# NILINET_POWER_PIR.net
KiCad netlist of a schematic drawn in Altium Designer
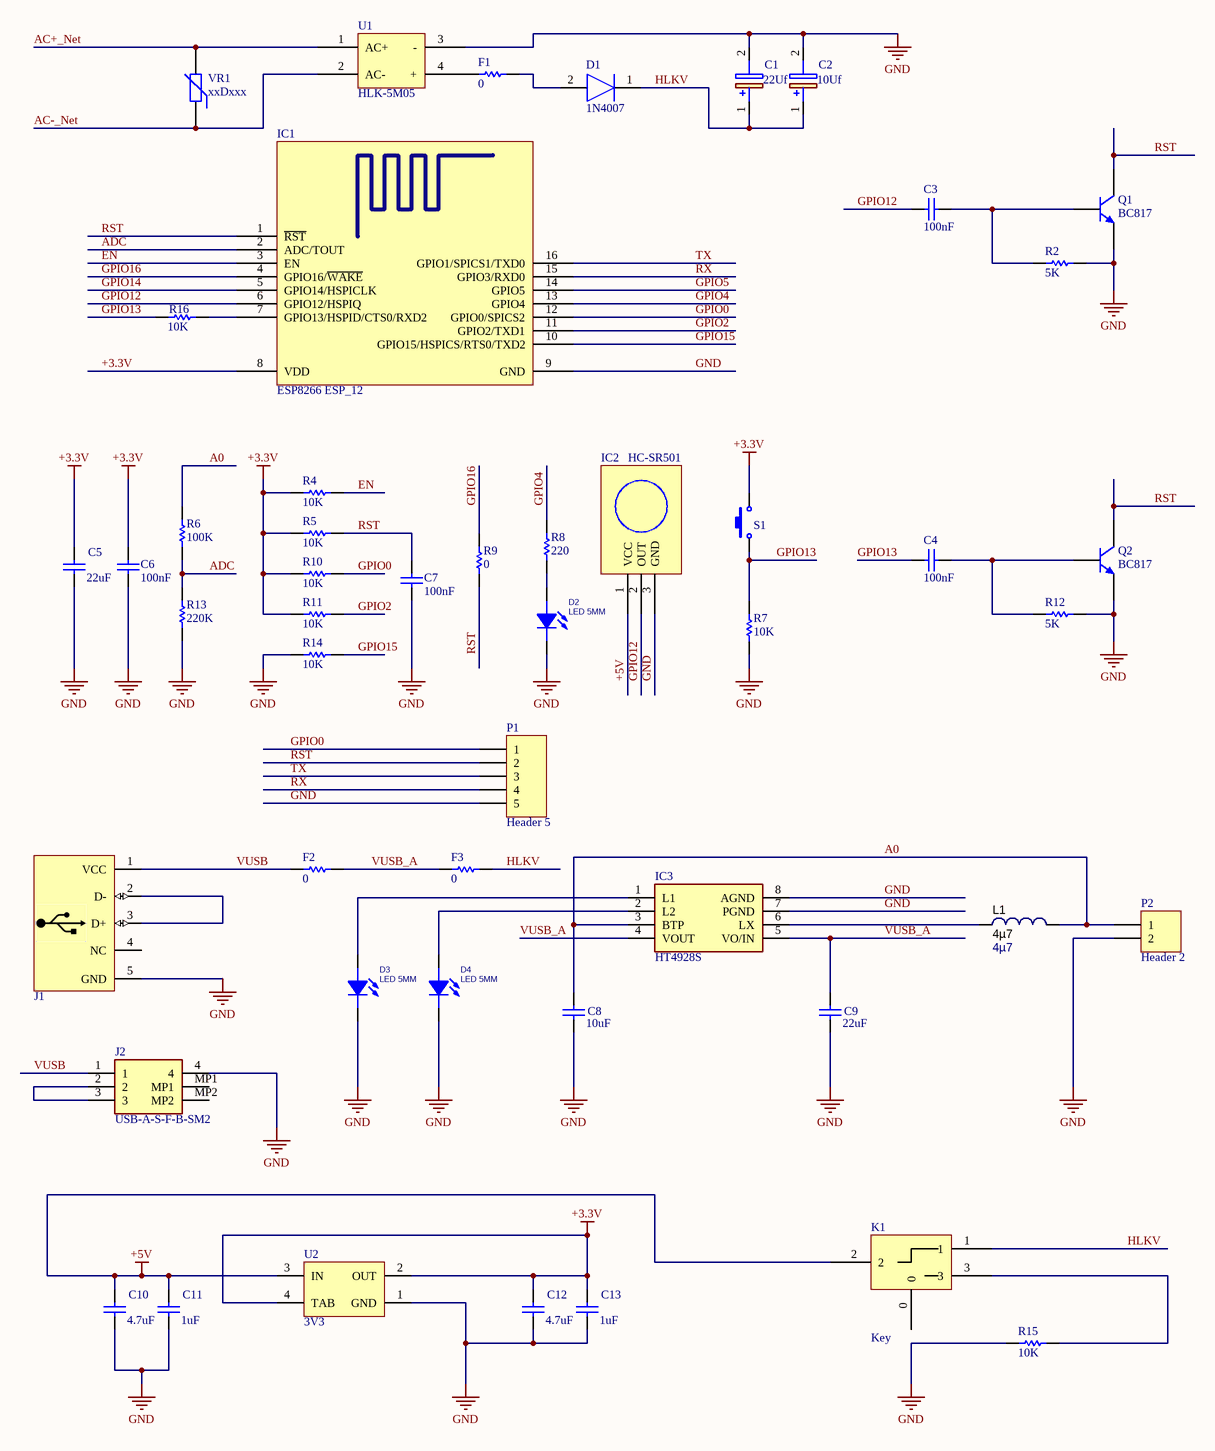
[diagram p0: NILINET_POWER_PIR.SchDoc]

(export (version "E")
  (design (tool "Eeschema 10.0.6"))
  (components
    (comp (ref "C1")
      (value "22Uf")
      (footprint "SamacSys:UWT(4X5.4)")
      (description "Capacitor Polarised")
      (fields
        (field (name "MANUFACTURER_PART_NUMBER") "UWT1C100MCL1GB")
        (field (name "MOUSER PART NUMBER") "647-UWT1C100MCL1B")
      )
      (libsource (lib "*") (part "UWT1C100MCL1GB"))
    )
    (comp (ref "C2")
      (value "10Uf")
      (footprint "SamacSys:UWT(4X5.4)")
      (description "Capacitor Polarised")
      (fields
        (field (name "MANUFACTURER_PART_NUMBER") "UWT1C100MCL1GB")
        (field (name "MOUSER PART NUMBER") "647-UWT1C100MCL1B")
      )
      (libsource (lib "*") (part "UWT1C100MCL1GB"))
    )
    (comp (ref "C3")
      (value "100nF")
      (footprint "CAP0603")
      (description "TOTAL CAPACITOR SMD PACK")
      (fields (field (name "DESIGNER") "Abbas Basereh"))
      (libsource (lib "Altium") (part "CAP SMD PACKAGE"))
    )
    (comp (ref "C4")
      (value "100nF")
      (footprint "CAP0603")
      (description "TOTAL CAPACITOR SMD PACK")
      (fields (field (name "DESIGNER") "Abbas Basereh"))
      (libsource (lib "Altium") (part "CAP SMD PACKAGE"))
    )
    (comp (ref "C5")
      (value "22uF")
      (footprint "CAP0805")
      (description "TOTAL CAPACITOR SMD PACK")
      (fields (field (name "DESIGNER") "Abbas Basereh"))
      (libsource (lib "Altium") (part "CAP SMD PACKAGE"))
    )
    (comp (ref "C6")
      (value "100nF")
      (footprint "CAP0603")
      (description "TOTAL CAPACITOR SMD PACK")
      (fields (field (name "DESIGNER") "Abbas Basereh"))
      (libsource (lib "Altium") (part "CAP SMD PACKAGE"))
    )
    (comp (ref "C7")
      (value "100nF")
      (footprint "CAP0603")
      (description "TOTAL CAPACITOR SMD PACK")
      (fields (field (name "DESIGNER") "Abbas Basereh"))
      (libsource (lib "Altium") (part "CAP SMD PACKAGE"))
    )
    (comp (ref "C8")
      (value "10uF")
      (footprint "CAP0805")
      (description "TOTAL CAPACITOR SMD PACK")
      (fields (field (name "DESIGNER") "Abbas Basereh"))
      (libsource (lib "Altium") (part "CAP SMD PACKAGE"))
    )
    (comp (ref "C9")
      (value "22uF")
      (footprint "CAP0805")
      (description "TOTAL CAPACITOR SMD PACK")
      (fields (field (name "DESIGNER") "Abbas Basereh"))
      (libsource (lib "Altium") (part "CAP SMD PACKAGE"))
    )
    (comp (ref "C10")
      (value "4.7uF")
      (footprint "CAP0805")
      (description "TOTAL CAPACITOR SMD PACK")
      (fields (field (name "DESIGNER") "Abbas Basereh"))
      (libsource (lib "Altium") (part "CAP SMD PACKAGE"))
    )
    (comp (ref "C11")
      (value "1uF")
      (footprint "CAP0805")
      (description "TOTAL CAPACITOR SMD PACK")
      (fields (field (name "DESIGNER") "Abbas Basereh"))
      (libsource (lib "Altium") (part "CAP SMD PACKAGE"))
    )
    (comp (ref "C12")
      (value "4.7uF")
      (footprint "CAP0805")
      (description "TOTAL CAPACITOR SMD PACK")
      (fields (field (name "DESIGNER") "Abbas Basereh"))
      (libsource (lib "Altium") (part "CAP SMD PACKAGE"))
    )
    (comp (ref "C13")
      (value "1uF")
      (footprint "CAP0805")
      (description "TOTAL CAPACITOR SMD PACK")
      (fields (field (name "DESIGNER") "Abbas Basereh"))
      (libsource (lib "Altium") (part "CAP SMD PACKAGE"))
    )
    (comp (ref "D1")
      (value "1N4007")
      (footprint "SamacSys:DIOM5327X242N")
      (description "Diode")
      (libsource (lib "*") (part "1N4007"))
    )
    (comp (ref "D2")
      (value "LED 5MM")
      (footprint "LED5MM_BLUE")
      (description "Light Emitting Diode")
      (fields (field (name "DESIGNER") "Abbas Basereh"))
      (libsource (lib "Altium") (part "LED 5MM"))
    )
    (comp (ref "D3")
      (value "LED 5MM")
      (footprint "LED5MM_RED")
      (description "Light Emitting Diode")
      (fields (field (name "DESIGNER") "Abbas Basereh"))
      (libsource (lib "Altium") (part "LED 5MM"))
    )
    (comp (ref "D4")
      (value "LED 5MM")
      (footprint "LED5MM_GRN")
      (description "Light Emitting Diode")
      (fields (field (name "DESIGNER") "Abbas Basereh"))
      (libsource (lib "Altium") (part "LED 5MM"))
    )
    (comp (ref "F1")
      (value "0")
      (footprint "RES0805")
      (description "TOTAL SMD RESISTOR PACK")
      (fields (field (name "DESIGNER") "Abbas Basereh"))
      (libsource (lib "Altium") (part "RES SMD PACKAGE"))
    )
    (comp (ref "F2")
      (value "0")
      (footprint "RES0805")
      (description "TOTAL SMD RESISTOR PACK")
      (fields (field (name "DESIGNER") "Abbas Basereh"))
      (libsource (lib "Altium") (part "RES SMD PACKAGE"))
    )
    (comp (ref "F3")
      (value "0")
      (footprint "RES0805")
      (description "TOTAL SMD RESISTOR PACK")
      (fields (field (name "DESIGNER") "Abbas Basereh"))
      (libsource (lib "Altium") (part "RES SMD PACKAGE"))
    )
    (comp (ref "IC1")
      (value "ESP8266 ESP_12")
      (footprint "ESP8266 ESP_12")
      (description "ESP8266 ESP-12")
      (fields (field (name "PUBLISHER") "Cynetik Group") (field (name "LATESTREVIEWER") "Zion Blue"))
      (libsource (lib "ESP8266") (part "ESP8266 ESP_12"))
    )
    (comp (ref "IC2")
      (value "HC-SR501")
      (footprint "jumper selector")
      (libsource (lib "HC-SR501") (part "HC-SR501"))
    )
    (comp (ref "IC3")
      (value "HT4928S")
      (footprint "SamacSys:SOIC127P600X180-8N")
      (description "Integrated Circuit")
      (libsource (lib "*") (part "HT4928S"))
    )
    (comp (ref "J1")
      (value "USB Connector")
      (footprint "MicroUSB111")
      (description "USB Connector MICRO-B Type")
      (fields (field (name "DESIGNER") "ABBAS BASEREH") (field (name "PUBLISHER") "ABBAS BASEREH"))
      (libsource (lib "Altium") (part "USB MICRO"))
    )
    (comp (ref "J2")
      (value "USB-A-S-F-B-SM2")
      (footprint "USBASFBSM3")
      (description "Connector")
      (fields (field (name "MOUSER PART NUMBER") "200-USBASFBSM2") (field (name "RS PART NUMBER") "1803451"))
      (libsource (lib "*") (part "USB-A-S-F-B-SM2"))
    )
    (comp (ref "K1") (value "Key") (footprint "Key") (libsource (lib "Key") (part "Key")))
    (comp (ref "L1")
      (value "4µ7")
      (footprint "Inductor SMD 3x3.2mm")
      (description "Inductor 4.7µH SMD 3x3.2mm")
      (fields (field (name "TOLERANCE") "±20%") (field (name "ALTIUM_VALUE") "4µ7"))
      (libsource (lib "General 1") (part "Inductor 4.7µH SMD 3x3.2mm"))
    )
    (comp (ref "P1")
      (value "Header 5")
      (footprint "HDR1X5")
      (description "Header, 5-Pin")
      (fields (field (name "PUBLISHER") "Altium Limited"))
      (libsource (lib "Altium") (part "Header 5"))
    )
    (comp (ref "P2")
      (value "Header 2")
      (footprint "HDR1X2")
      (description "Header, 2-Pin")
      (fields (field (name "PUBLISHER") "Altium Limited"))
      (libsource (lib "Altium") (part "Header 2"))
    )
    (comp (ref "Q1")
      (value "BC817")
      (footprint "SOT23_N")
      (description "45 V, 500 mA NPN general-purpose transistors")
      (fields (field (name "PUBLISHER") "Abbas Basereh"))
      (libsource (lib "General 1") (part "BC817"))
    )
    (comp (ref "Q2")
      (value "BC817")
      (footprint "SOT23_N")
      (description "45 V, 500 mA NPN general-purpose transistors")
      (fields (field (name "PUBLISHER") "Abbas Basereh"))
      (libsource (lib "General 1") (part "BC817"))
    )
    (comp (ref "R2")
      (value "5K")
      (footprint "RES0603")
      (description "TOTAL SMD RESISTOR PACK")
      (fields (field (name "DESIGNER") "Abbas Basereh"))
      (libsource (lib "Altium") (part "RES SMD PACKAGE"))
    )
    (comp (ref "R4")
      (value "10K")
      (footprint "RES0603")
      (description "TOTAL SMD RESISTOR PACK")
      (fields (field (name "DESIGNER") "Abbas Basereh"))
      (libsource (lib "Altium") (part "RES SMD PACKAGE"))
    )
    (comp (ref "R5")
      (value "10K")
      (footprint "RES0603")
      (description "TOTAL SMD RESISTOR PACK")
      (fields (field (name "DESIGNER") "Abbas Basereh"))
      (libsource (lib "Altium") (part "RES SMD PACKAGE"))
    )
    (comp (ref "R6")
      (value "100K")
      (footprint "RES0603")
      (description "TOTAL SMD RESISTOR PACK")
      (fields (field (name "DESIGNER") "Abbas Basereh"))
      (libsource (lib "Altium") (part "RES SMD PACKAGE"))
    )
    (comp (ref "R7")
      (value "10K")
      (footprint "RES0603")
      (description "TOTAL SMD RESISTOR PACK")
      (fields (field (name "DESIGNER") "Abbas Basereh"))
      (libsource (lib "Altium") (part "RES SMD PACKAGE"))
    )
    (comp (ref "R8")
      (value "220")
      (footprint "RES0603")
      (description "TOTAL SMD RESISTOR PACK")
      (fields (field (name "DESIGNER") "Abbas Basereh"))
      (libsource (lib "Altium") (part "RES SMD PACKAGE"))
    )
    (comp (ref "R9")
      (value "0")
      (footprint "RES0603")
      (description "TOTAL SMD RESISTOR PACK")
      (fields (field (name "DESIGNER") "Abbas Basereh"))
      (libsource (lib "Altium") (part "RES SMD PACKAGE"))
    )
    (comp (ref "R10")
      (value "10K")
      (footprint "RES0603")
      (description "TOTAL SMD RESISTOR PACK")
      (fields (field (name "DESIGNER") "Abbas Basereh"))
      (libsource (lib "Altium") (part "RES SMD PACKAGE"))
    )
    (comp (ref "R11")
      (value "10K")
      (footprint "RES0603")
      (description "TOTAL SMD RESISTOR PACK")
      (fields (field (name "DESIGNER") "Abbas Basereh"))
      (libsource (lib "Altium") (part "RES SMD PACKAGE"))
    )
    (comp (ref "R12")
      (value "5K")
      (footprint "RES0603")
      (description "TOTAL SMD RESISTOR PACK")
      (fields (field (name "DESIGNER") "Abbas Basereh"))
      (libsource (lib "Altium") (part "RES SMD PACKAGE"))
    )
    (comp (ref "R13")
      (value "220K")
      (footprint "RES0603")
      (description "TOTAL SMD RESISTOR PACK")
      (fields (field (name "DESIGNER") "Abbas Basereh"))
      (libsource (lib "Altium") (part "RES SMD PACKAGE"))
    )
    (comp (ref "R14")
      (value "10K")
      (footprint "RES0603")
      (description "TOTAL SMD RESISTOR PACK")
      (fields (field (name "DESIGNER") "Abbas Basereh"))
      (libsource (lib "Altium") (part "RES SMD PACKAGE"))
    )
    (comp (ref "R15")
      (value "10K")
      (footprint "RES0603")
      (description "TOTAL SMD RESISTOR PACK")
      (fields (field (name "DESIGNER") "Abbas Basereh"))
      (libsource (lib "Altium") (part "RES SMD PACKAGE"))
    )
    (comp (ref "R16")
      (value "10K")
      (footprint "RES0603")
      (description "TOTAL SMD RESISTOR PACK")
      (fields (field (name "DESIGNER") "Abbas Basereh"))
      (libsource (lib "Altium") (part "RES SMD PACKAGE"))
    )
    (comp (ref "S1")
      (value "Switch PB")
      (footprint "SwitchRight")
      (description "Push Button Switch")
      (libsource (lib "Altium") (part "Switch PB"))
    )
    (comp (ref "U1") (value "HLK-5M05") (footprint "HLK-5M05") (libsource (lib "HLK-5M05") (part "HLK-PM01")))
    (comp (ref "U2")
      (value "3V3")
      (footprint "SOT223")
      (description "x.x Volt, 800mA Low-Dropout Linear Regulator, 4-pin SOT-223")
      (fields (field (name "DESIGNER") "Ali Hafizi"))
      (libsource (lib "Altium") (part "AMS1117-x.x"))
    )
    (comp (ref "VR1")
      (value "xxDxxx")
      (footprint "10D XXX")
      (description "VARISTORS")
      (fields
        (field (name "MANUFACTURER") "china-canada-philipina")
        (field (name "DESIGNER") "Abbas Basereh")
        (field (name "PUBLISHER") "ABBAS BASEREH")
      )
      (libsource (lib "Altium") (part "VARISTOR (VDR)"))
    )
  )
  (nets
    (net (code "1") (name "+3.3V") (class "Default")
      (node (ref "C12") (pin "2") (pinfunction "2_2") (pintype "passive"))
      (node (ref "C13") (pin "2") (pinfunction "2_2") (pintype "passive"))
      (node (ref "C5") (pin "2") (pinfunction "2_2") (pintype "passive"))
      (node (ref "C6") (pin "2") (pinfunction "2_2") (pintype "passive"))
      (node (ref "IC1") (pin "8") (pinfunction "VDD_8") (pintype "passive"))
      (node (ref "R10") (pin "2") (pinfunction "2_2") (pintype "passive"))
      (node (ref "R11") (pin "2") (pinfunction "2_2") (pintype "passive"))
      (node (ref "R4") (pin "2") (pinfunction "2_2") (pintype "passive"))
      (node (ref "R5") (pin "2") (pinfunction "2_2") (pintype "passive"))
      (node (ref "S1") (pin "2") (pinfunction "2_2") (pintype "passive"))
      (node (ref "U2") (pin "2") (pinfunction "OUT_2") (pintype "power_in"))
      (node (ref "U2") (pin "4") (pinfunction "TAB_4") (pintype "power_in"))
    )
    (net (code "2") (name "+5V") (class "Default")
      (node (ref "C10") (pin "2") (pinfunction "2_2") (pintype "passive"))
      (node (ref "C11") (pin "2") (pinfunction "2_2") (pintype "passive"))
      (node (ref "IC2") (pin "1") (pinfunction "VCC_1") (pintype "passive"))
      (node (ref "K1") (pin "2") (pinfunction "2_2") (pintype "passive"))
      (node (ref "U2") (pin "3") (pinfunction "IN_3") (pintype "power_in"))
    )
    (net (code "3") (name "/A0") (class "Default")
      (node (ref "C8") (pin "2") (pinfunction "2_2") (pintype "passive"))
      (node (ref "IC3") (pin "3") (pinfunction "BTP_3") (pintype "passive"))
      (node (ref "L1") (pin "2") (pinfunction "2_2") (pintype "passive"))
      (node (ref "P2") (pin "1") (pinfunction "1_1") (pintype "passive"))
      (node (ref "R6") (pin "2") (pinfunction "2_2") (pintype "passive"))
    )
    (net (code "4") (name "/AC+_Net") (class "Default")
      (node (ref "U1") (pin "1") (pinfunction "AC+_1") (pintype "passive"))
      (node (ref "VR1") (pin "2") (pinfunction "2_2") (pintype "passive"))
    )
    (net (code "5") (name "/AC-_Net") (class "Default")
      (node (ref "U1") (pin "2") (pinfunction "AC-_2") (pintype "passive"))
      (node (ref "VR1") (pin "1") (pinfunction "1_1") (pintype "passive"))
    )
    (net (code "6") (name "/ADC") (class "Default")
      (node (ref "IC1") (pin "2") (pinfunction "ADC/TOUT_2") (pintype "passive"))
      (node (ref "R13") (pin "2") (pinfunction "2_2") (pintype "passive"))
      (node (ref "R6") (pin "1") (pinfunction "1_1") (pintype "passive"))
    )
    (net (code "7") (name "/EN") (class "Default")
      (node (ref "IC1") (pin "3") (pinfunction "EN_3") (pintype "passive"))
      (node (ref "R4") (pin "1") (pinfunction "1_1") (pintype "passive"))
    )
    (net (code "8") (name "/GPIO0") (class "Default")
      (node (ref "IC1") (pin "12") (pinfunction "GPIO0/SPICS2_12") (pintype "passive"))
      (node (ref "P1") (pin "1") (pinfunction "1_1") (pintype "passive"))
      (node (ref "R10") (pin "1") (pinfunction "1_1") (pintype "passive"))
    )
    (net (code "9") (name "/GPIO2") (class "Default")
      (node (ref "IC1") (pin "11") (pinfunction "GPIO2/TXD1_11") (pintype "passive"))
      (node (ref "R11") (pin "1") (pinfunction "1_1") (pintype "passive"))
    )
    (net (code "10") (name "/GPIO4") (class "Default")
      (node (ref "IC1") (pin "13") (pinfunction "GPIO4_13") (pintype "passive"))
      (node (ref "R8") (pin "1") (pinfunction "1_1") (pintype "passive"))
    )
    (net (code "11") (name "/GPIO5") (class "Default")
      (node (ref "IC1") (pin "14") (pinfunction "GPIO5_14") (pintype "passive"))
    )
    (net (code "12") (name "/GPIO12") (class "Default")
      (node (ref "C3") (pin "2") (pinfunction "2_2") (pintype "passive"))
      (node (ref "IC1") (pin "6") (pinfunction "GPIO12/HSPIQ_6") (pintype "passive"))
      (node (ref "IC2") (pin "2") (pinfunction "OUT_2") (pintype "passive"))
    )
    (net (code "13") (name "/GPIO13") (class "Default")
      (node (ref "C4") (pin "2") (pinfunction "2_2") (pintype "passive"))
      (node (ref "R16") (pin "2") (pinfunction "2_2") (pintype "passive"))
      (node (ref "R7") (pin "1") (pinfunction "1_1") (pintype "passive"))
      (node (ref "S1") (pin "1") (pinfunction "1_1") (pintype "passive"))
    )
    (net (code "14") (name "/GPIO14") (class "Default")
      (node (ref "IC1") (pin "5") (pinfunction "GPIO14/HSPICLK_5") (pintype "passive"))
    )
    (net (code "15") (name "/GPIO15") (class "Default")
      (node (ref "IC1") (pin "10") (pinfunction "GPIO15/HSPICS/RTS0/TXD2_10") (pintype "passive"))
      (node (ref "R14") (pin "1") (pinfunction "1_1") (pintype "passive"))
    )
    (net (code "16") (name "/GPIO16") (class "Default")
      (node (ref "IC1") (pin "4") (pinfunction "GPIO16/~{WAKE}_4") (pintype "passive"))
      (node (ref "R9") (pin "1") (pinfunction "1_1") (pintype "passive"))
    )
    (net (code "17") (name "/HLKV") (class "Default")
      (node (ref "C1") (pin "1") (pinfunction "+_1") (pintype "passive"))
      (node (ref "C2") (pin "1") (pinfunction "+_1") (pintype "passive"))
      (node (ref "D1") (pin "1") (pinfunction "K_1") (pintype "passive"))
      (node (ref "F3") (pin "1") (pinfunction "1_1") (pintype "passive"))
      (node (ref "K1") (pin "1") (pinfunction "1_1") (pintype "passive"))
    )
    (net (code "18") (name "/RST") (class "Default")
      (node (ref "C7") (pin "2") (pinfunction "2_2") (pintype "passive"))
      (node (ref "IC1") (pin "1") (pinfunction "~{RST}_1") (pintype "passive"))
      (node (ref "P1") (pin "2") (pinfunction "2_2") (pintype "passive"))
      (node (ref "Q1") (pin "3") (pinfunction "C_3") (pintype "passive"))
      (node (ref "Q2") (pin "3") (pinfunction "C_3") (pintype "passive"))
      (node (ref "R5") (pin "1") (pinfunction "1_1") (pintype "passive"))
      (node (ref "R9") (pin "2") (pinfunction "2_2") (pintype "passive"))
    )
    (net (code "19") (name "/RX") (class "Default")
      (node (ref "IC1") (pin "15") (pinfunction "GPIO3/RXD0_15") (pintype "passive"))
      (node (ref "P1") (pin "4") (pinfunction "4_4") (pintype "passive"))
    )
    (net (code "20") (name "/TX") (class "Default")
      (node (ref "IC1") (pin "16") (pinfunction "GPIO1/SPICS1/TXD0_16") (pintype "passive"))
      (node (ref "P1") (pin "3") (pinfunction "3_3") (pintype "passive"))
    )
    (net (code "21") (name "/VUSB") (class "Default")
      (node (ref "F2") (pin "2") (pinfunction "2_2") (pintype "passive"))
      (node (ref "J1") (pin "1") (pinfunction "VCC_1") (pintype "power_in"))
      (node (ref "J2") (pin "1") (pinfunction "1_1") (pintype "passive"))
    )
    (net (code "22") (name "/VUSB_A") (class "Default")
      (node (ref "C9") (pin "2") (pinfunction "2_2") (pintype "passive"))
      (node (ref "F2") (pin "1") (pinfunction "1_1") (pintype "passive"))
      (node (ref "F3") (pin "2") (pinfunction "2_2") (pintype "passive"))
      (node (ref "IC3") (pin "4") (pinfunction "VOUT_4") (pintype "passive"))
      (node (ref "IC3") (pin "5") (pinfunction "VO/IN_5") (pintype "passive"))
    )
    (net (code "23") (name "GND") (class "Default")
      (node (ref "C1") (pin "2") (pinfunction "-_2") (pintype "passive"))
      (node (ref "C10") (pin "1") (pinfunction "1_1") (pintype "passive"))
      (node (ref "C11") (pin "1") (pinfunction "1_1") (pintype "passive"))
      (node (ref "C12") (pin "1") (pinfunction "1_1") (pintype "passive"))
      (node (ref "C13") (pin "1") (pinfunction "1_1") (pintype "passive"))
      (node (ref "C2") (pin "2") (pinfunction "-_2") (pintype "passive"))
      (node (ref "C5") (pin "1") (pinfunction "1_1") (pintype "passive"))
      (node (ref "C6") (pin "1") (pinfunction "1_1") (pintype "passive"))
      (node (ref "C7") (pin "1") (pinfunction "1_1") (pintype "passive"))
      (node (ref "C8") (pin "1") (pinfunction "1_1") (pintype "passive"))
      (node (ref "C9") (pin "1") (pinfunction "1_1") (pintype "passive"))
      (node (ref "D2") (pin "2") (pinfunction "CATHODE_2") (pintype "passive"))
      (node (ref "D3") (pin "2") (pinfunction "CATHODE_2") (pintype "passive"))
      (node (ref "D4") (pin "2") (pinfunction "CATHODE_2") (pintype "passive"))
      (node (ref "IC1") (pin "9") (pinfunction "GND_9") (pintype "passive"))
      (node (ref "IC2") (pin "3") (pinfunction "GND_3") (pintype "passive"))
      (node (ref "IC3") (pin "7") (pinfunction "PGND_7") (pintype "passive"))
      (node (ref "IC3") (pin "8") (pinfunction "AGND_8") (pintype "passive"))
      (node (ref "J1") (pin "5") (pinfunction "GND_5") (pintype "power_in"))
      (node (ref "J2") (pin "4") (pinfunction "4_4") (pintype "passive"))
      (node (ref "P1") (pin "5") (pinfunction "5_5") (pintype "passive"))
      (node (ref "P2") (pin "2") (pinfunction "2_2") (pintype "passive"))
      (node (ref "Q1") (pin "2") (pinfunction "E_2") (pintype "passive"))
      (node (ref "Q2") (pin "2") (pinfunction "E_2") (pintype "passive"))
      (node (ref "R12") (pin "1") (pinfunction "1_1") (pintype "passive"))
      (node (ref "R13") (pin "1") (pinfunction "1_1") (pintype "passive"))
      (node (ref "R14") (pin "2") (pinfunction "2_2") (pintype "passive"))
      (node (ref "R15") (pin "2") (pinfunction "2_2") (pintype "passive"))
      (node (ref "R2") (pin "1") (pinfunction "1_1") (pintype "passive"))
      (node (ref "R7") (pin "2") (pinfunction "2_2") (pintype "passive"))
      (node (ref "U1") (pin "3") (pinfunction "-_3") (pintype "passive"))
      (node (ref "U2") (pin "1") (pinfunction "GND_1") (pintype "power_in"))
    )
    (net (code "24") (name "Net-(D1-A)") (class "Default")
      (node (ref "D1") (pin "2") (pinfunction "A_2") (pintype "passive"))
      (node (ref "F1") (pin "1") (pinfunction "1_1") (pintype "passive"))
    )
    (net (code "25") (name "Net-(D2-ANODE)") (class "Default")
      (node (ref "D2") (pin "1") (pinfunction "ANODE_1") (pintype "passive"))
      (node (ref "R8") (pin "2") (pinfunction "2_2") (pintype "passive"))
    )
    (net (code "26") (name "Net-(D3-ANODE)") (class "Default")
      (node (ref "D3") (pin "1") (pinfunction "ANODE_1") (pintype "passive"))
      (node (ref "IC3") (pin "1") (pinfunction "L1_1") (pintype "passive"))
    )
    (net (code "27") (name "Net-(D4-ANODE)") (class "Default")
      (node (ref "D4") (pin "1") (pinfunction "ANODE_1") (pintype "passive"))
      (node (ref "IC3") (pin "2") (pinfunction "L2_2") (pintype "passive"))
    )
    (net (code "28") (name "Net-(IC1-GPIO13{slash}HSPID{slash}CTS0{slash}RXD2)") (class "Default")
      (node (ref "IC1") (pin "7") (pinfunction "GPIO13/HSPID/CTS0/RXD2_7") (pintype "passive"))
      (node (ref "R16") (pin "1") (pinfunction "1_1") (pintype "passive"))
    )
    (net (code "29") (name "Net-(IC3-LX)") (class "Default")
      (node (ref "IC3") (pin "6") (pinfunction "LX_6") (pintype "passive"))
      (node (ref "L1") (pin "1") (pinfunction "1_1") (pintype "passive"))
    )
    (net (code "30") (name "Net-(J1-D+)") (class "Default")
      (node (ref "J1") (pin "2") (pinfunction "D-_2") (pintype "bidirectional"))
      (node (ref "J1") (pin "3") (pinfunction "D+_3") (pintype "bidirectional"))
    )
    (net (code "31") (name "Net-(J2-Pad2)") (class "Default")
      (node (ref "J2") (pin "2") (pinfunction "2_2") (pintype "passive"))
      (node (ref "J2") (pin "3") (pinfunction "3_3") (pintype "passive"))
    )
    (net (code "32") (name "Net-(K1-Pad3)") (class "Default")
      (node (ref "K1") (pin "3") (pinfunction "3_3") (pintype "passive"))
      (node (ref "R15") (pin "1") (pinfunction "1_1") (pintype "passive"))
    )
    (net (code "33") (name "Net-(Q1-B)") (class "Default")
      (node (ref "C3") (pin "1") (pinfunction "1_1") (pintype "passive"))
      (node (ref "Q1") (pin "1") (pinfunction "B_1") (pintype "passive"))
      (node (ref "R2") (pin "2") (pinfunction "2_2") (pintype "passive"))
    )
    (net (code "34") (name "Net-(Q2-B)") (class "Default")
      (node (ref "C4") (pin "1") (pinfunction "1_1") (pintype "passive"))
      (node (ref "Q2") (pin "1") (pinfunction "B_1") (pintype "passive"))
      (node (ref "R12") (pin "2") (pinfunction "2_2") (pintype "passive"))
    )
    (net (code "35") (name "Net-(U1-+)") (class "Default")
      (node (ref "F1") (pin "2") (pinfunction "2_2") (pintype "passive"))
      (node (ref "U1") (pin "4") (pinfunction "+_4") (pintype "passive"))
    )
    (net (code "36") (name "unconnected-(J1-NC-Pad4)") (class "Default")
      (node (ref "J1") (pin "4") (pinfunction "NC_4") (pintype "passive"))
    )
    (net (code "37") (name "unconnected-(J2-PadMP1)") (class "Default")
      (node (ref "J2") (pin "MP1") (pinfunction "MP1_MP1") (pintype "passive"))
    )
    (net (code "38") (name "unconnected-(J2-PadMP2)") (class "Default")
      (node (ref "J2") (pin "MP2") (pinfunction "MP2_MP2") (pintype "passive"))
    )
    (net (code "39") (name "unconnected-(K1-Pad0)") (class "Default")
      (node (ref "K1") (pin "0") (pinfunction "0_0") (pintype "passive"))
    )
  )
)
